# core_manual.net
KiCad netlist of a schematic drawn in EAGLE
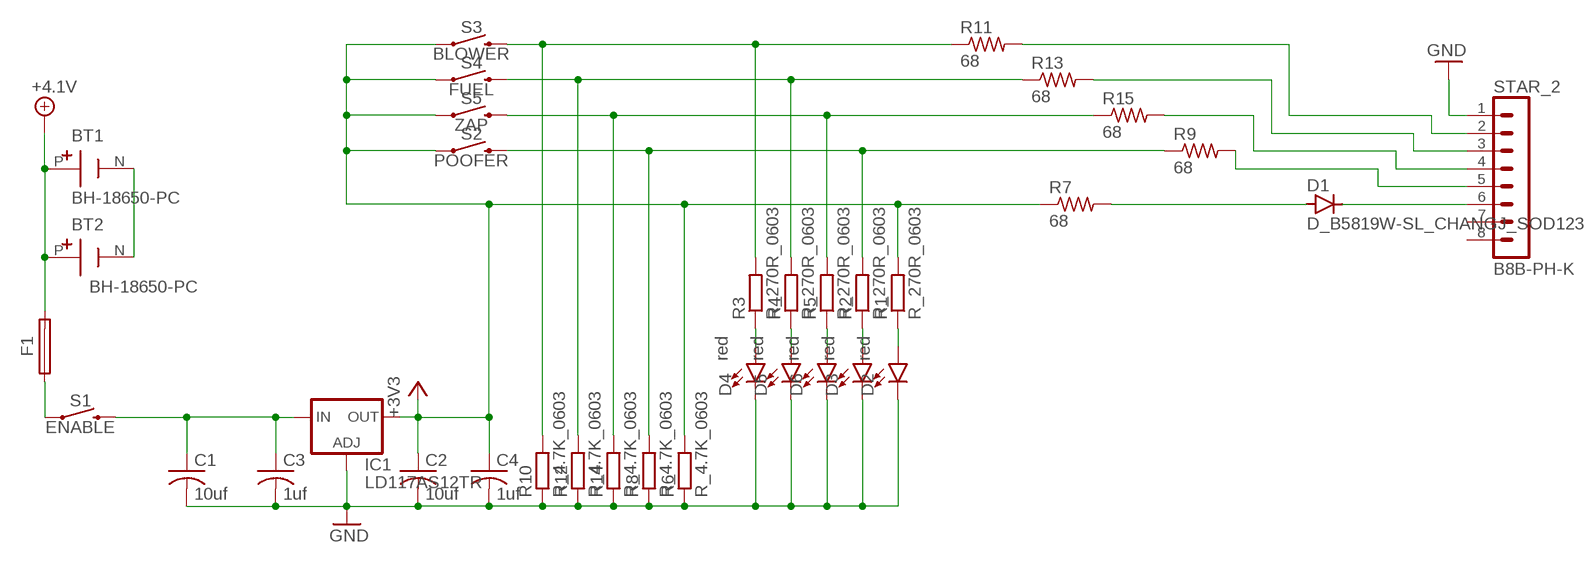
[diagram p0: schematic, sheet 1]

(export (version "E")
  (design (tool "Eeschema 10.0.6"))
  (components
    (comp (ref "BT1")
      (value "BH-18650-PC")
      (footprint "eagle-import:BAT_BH-18650-PC")
      (fields (field (name "MF") "MPD"))
      (libsource (lib "eagle-import") (part "BH-18650-PC"))
    )
    (comp (ref "BT2")
      (value "BH-18650-PC")
      (footprint "eagle-import:BAT_BH-18650-PC")
      (fields (field (name "MF") "MPD"))
      (libsource (lib "eagle-import") (part "BH-18650-PC"))
    )
    (comp (ref "C1")
      (value "10uf")
      (footprint "eagle-import:C0603")
      (fields (field (name "LCSC_PART") "C19702"))
      (libsource (lib "eagle-import") (part "C-USC0603"))
    )
    (comp (ref "C2")
      (value "10uf")
      (footprint "eagle-import:C0603")
      (fields (field (name "LCSC_PART") "C19702"))
      (libsource (lib "eagle-import") (part "C-USC0603"))
    )
    (comp (ref "C3")
      (value "1uf")
      (footprint "eagle-import:C0805")
      (fields (field (name "LCSC_PART") "C15849"))
      (libsource (lib "eagle-import") (part "C-USC0805"))
    )
    (comp (ref "C4")
      (value "1uf")
      (footprint "eagle-import:C0805")
      (fields (field (name "LCSC_PART") "C15849"))
      (libsource (lib "eagle-import") (part "C-USC0805"))
    )
    (comp (ref "D1")
      (value "D_B5819W-SL_CHANGJ_SOD123")
      (footprint "eagle-import:SOD123")
      (fields (field (name "LCSC_PART") "C8598"))
      (libsource (lib "eagle-import") (part "D__SOD123B5819W-SL_CHANGJ"))
    )
    (comp (ref "D2")
      (value "red")
      (footprint "eagle-import:LED-0603")
      (fields (field (name "LCSC_PART") "C2286"))
      (libsource (lib "eagle-import") (part "LED0603"))
    )
    (comp (ref "D3")
      (value "red")
      (footprint "eagle-import:LED-0603")
      (fields (field (name "LCSC_PART") "C2286"))
      (libsource (lib "eagle-import") (part "LED0603"))
    )
    (comp (ref "D4")
      (value "red")
      (footprint "eagle-import:LED-0603")
      (fields (field (name "LCSC_PART") "C2286"))
      (libsource (lib "eagle-import") (part "LED0603"))
    )
    (comp (ref "D5")
      (value "red")
      (footprint "eagle-import:LED-0603")
      (fields (field (name "LCSC_PART") "C2286"))
      (libsource (lib "eagle-import") (part "LED0603"))
    )
    (comp (ref "D6")
      (value "red")
      (footprint "eagle-import:LED-0603")
      (fields (field (name "LCSC_PART") "C2286"))
      (libsource (lib "eagle-import") (part "LED0603"))
    )
    (comp (ref "F1")
      (value "MF-MSMF-STYLE2_1")
      (footprint "eagle-import:FUSC4632X160")
      (fields
        (field (name "MANUFACTURER") "BOURNS")
        (field (name "MPN") "MF-MSMF")
        (field (name "LCSC_PART") "C78695")
      )
      (libsource (lib "eagle-import") (part "MF-MSMF-STYLE2_1"))
    )
    (comp (ref "IC1")
      (value "LD117AS12TR")
      (footprint "eagle-import:SOT223")
      (fields (field (name "LCSC_PART") "C347222"))
      (libsource (lib "eagle-import") (part "LD117A?S12TR"))
    )
    (comp (ref "R1")
      (value "R_270R_0603")
      (footprint "eagle-import:R0603")
      (fields (field (name "LCSC_PART") "C22966"))
      (libsource (lib "eagle-import") (part "R__0603270R"))
    )
    (comp (ref "R2")
      (value "R_270R_0603")
      (footprint "eagle-import:R0603")
      (fields (field (name "LCSC_PART") "C22966"))
      (libsource (lib "eagle-import") (part "R__0603270R"))
    )
    (comp (ref "R3")
      (value "R_270R_0603")
      (footprint "eagle-import:R0603")
      (fields (field (name "LCSC_PART") "C22966"))
      (libsource (lib "eagle-import") (part "R__0603270R"))
    )
    (comp (ref "R4")
      (value "R_270R_0603")
      (footprint "eagle-import:R0603")
      (fields (field (name "LCSC_PART") "C22966"))
      (libsource (lib "eagle-import") (part "R__0603270R"))
    )
    (comp (ref "R5")
      (value "R_270R_0603")
      (footprint "eagle-import:R0603")
      (fields (field (name "LCSC_PART") "C22966"))
      (libsource (lib "eagle-import") (part "R__0603270R"))
    )
    (comp (ref "R6")
      (value "R_4.7K_0603")
      (footprint "eagle-import:R0603")
      (fields (field (name "LCSC_PART") "C23162"))
      (libsource (lib "eagle-import") (part "R__06034.7K"))
    )
    (comp (ref "R7")
      (value "68")
      (footprint "eagle-import:R0603")
      (fields (field (name "LCSC_PART") "c27592"))
      (libsource (lib "eagle-import") (part "R-US_R0603"))
    )
    (comp (ref "R8")
      (value "R_4.7K_0603")
      (footprint "eagle-import:R0603")
      (fields (field (name "LCSC_PART") "C23162"))
      (libsource (lib "eagle-import") (part "R__06034.7K"))
    )
    (comp (ref "R9")
      (value "68")
      (footprint "eagle-import:R0603")
      (fields (field (name "LCSC_PART") "c27592"))
      (libsource (lib "eagle-import") (part "R-US_R0603"))
    )
    (comp (ref "R10")
      (value "R_4.7K_0603")
      (footprint "eagle-import:R0603")
      (fields (field (name "LCSC_PART") "C23162"))
      (libsource (lib "eagle-import") (part "R__06034.7K"))
    )
    (comp (ref "R11")
      (value "68")
      (footprint "eagle-import:R0603")
      (fields (field (name "LCSC_PART") "c27592"))
      (libsource (lib "eagle-import") (part "R-US_R0603"))
    )
    (comp (ref "R12")
      (value "R_4.7K_0603")
      (footprint "eagle-import:R0603")
      (fields (field (name "LCSC_PART") "C23162"))
      (libsource (lib "eagle-import") (part "R__06034.7K"))
    )
    (comp (ref "R13")
      (value "68")
      (footprint "eagle-import:R0603")
      (fields (field (name "LCSC_PART") "c27592"))
      (libsource (lib "eagle-import") (part "R-US_R0603"))
    )
    (comp (ref "R14")
      (value "R_4.7K_0603")
      (footprint "eagle-import:R0603")
      (fields (field (name "LCSC_PART") "C23162"))
      (libsource (lib "eagle-import") (part "R__06034.7K"))
    )
    (comp (ref "R15")
      (value "68")
      (footprint "eagle-import:R0603")
      (fields (field (name "LCSC_PART") "c27592"))
      (libsource (lib "eagle-import") (part "R-US_R0603"))
    )
    (comp (ref "S1")
      (value "ENABLE")
      (footprint "eagle-import:TACTILE_SWITCH_PTH_6.0MM")
      (libsource (lib "eagle-import") (part "MOMENTARY-SWITCH-SPST-PTH-6.0MM"))
    )
    (comp (ref "S2")
      (value "POOFER")
      (footprint "eagle-import:TACTILE_SWITCH_PTH_6.0MM")
      (libsource (lib "eagle-import") (part "MOMENTARY-SWITCH-SPST-PTH-6.0MM"))
    )
    (comp (ref "S3")
      (value "BLOWER")
      (footprint "eagle-import:TACTILE_SWITCH_PTH_6.0MM")
      (libsource (lib "eagle-import") (part "MOMENTARY-SWITCH-SPST-PTH-6.0MM"))
    )
    (comp (ref "S4")
      (value "FUEL")
      (footprint "eagle-import:TACTILE_SWITCH_PTH_6.0MM")
      (libsource (lib "eagle-import") (part "MOMENTARY-SWITCH-SPST-PTH-6.0MM"))
    )
    (comp (ref "S5")
      (value "ZAP")
      (footprint "eagle-import:TACTILE_SWITCH_PTH_6.0MM")
      (libsource (lib "eagle-import") (part "MOMENTARY-SWITCH-SPST-PTH-6.0MM"))
    )
    (comp (ref "STAR_2")
      (value "B8B-PH-K")
      (footprint "eagle-import:B8B-PH-K")
      (libsource (lib "eagle-import") (part "B8B-PH-K"))
    )
  )
  (nets
    (net (code "1") (name "+3V3") (class "Default")
      (node (ref "C2") (pin "1") (pinfunction "1_1") (pintype "passive"))
      (node (ref "C4") (pin "1") (pinfunction "1_1") (pintype "passive"))
      (node (ref "IC1") (pin "4") (pinfunction "OUT_4") (pintype "passive"))
      (node (ref "R1") (pin "2") (pinfunction "2_2") (pintype "passive"))
      (node (ref "R6") (pin "2") (pinfunction "2_2") (pintype "passive"))
      (node (ref "R7") (pin "1") (pinfunction "1_1") (pintype "passive"))
      (node (ref "S2") (pin "1") (pinfunction "1_1") (pintype "passive"))
      (node (ref "S3") (pin "1") (pinfunction "1_1") (pintype "passive"))
      (node (ref "S4") (pin "1") (pinfunction "1_1") (pintype "passive"))
      (node (ref "S5") (pin "1") (pinfunction "1_1") (pintype "passive"))
    )
    (net (code "2") (name "+4.1V") (class "Default")
      (node (ref "BT1") (pin "P") (pinfunction "+_P") (pintype "passive"))
      (node (ref "BT2") (pin "P") (pinfunction "+_P") (pintype "passive"))
      (node (ref "F1") (pin "2") (pinfunction "2_2") (pintype "passive"))
    )
    (net (code "3") (name "GND") (class "Default")
      (node (ref "C1") (pin "2") (pinfunction "2_2") (pintype "passive"))
      (node (ref "C2") (pin "2") (pinfunction "2_2") (pintype "passive"))
      (node (ref "C3") (pin "2") (pinfunction "2_2") (pintype "passive"))
      (node (ref "C4") (pin "2") (pinfunction "2_2") (pintype "passive"))
      (node (ref "D2") (pin "C") (pinfunction "C_C") (pintype "passive"))
      (node (ref "D3") (pin "C") (pinfunction "C_C") (pintype "passive"))
      (node (ref "D4") (pin "C") (pinfunction "C_C") (pintype "passive"))
      (node (ref "D5") (pin "C") (pinfunction "C_C") (pintype "passive"))
      (node (ref "D6") (pin "C") (pinfunction "C_C") (pintype "passive"))
      (node (ref "IC1") (pin "1") (pinfunction "ADJ_1") (pintype "input"))
      (node (ref "R10") (pin "1") (pinfunction "1_1") (pintype "passive"))
      (node (ref "R12") (pin "1") (pinfunction "1_1") (pintype "passive"))
      (node (ref "R14") (pin "1") (pinfunction "1_1") (pintype "passive"))
      (node (ref "R6") (pin "1") (pinfunction "1_1") (pintype "passive"))
      (node (ref "R8") (pin "1") (pinfunction "1_1") (pintype "passive"))
      (node (ref "STAR_2") (pin "1") (pinfunction "1_1") (pintype "passive"))
    )
    (net (code "4") (name "Net-(BT1--)") (class "Default")
      (node (ref "BT1") (pin "N") (pinfunction "-_N") (pintype "passive"))
      (node (ref "BT2") (pin "N") (pinfunction "-_N") (pintype "passive"))
    )
    (net (code "5") (name "Net-(D1-PadA)") (class "Default")
      (node (ref "D1") (pin "A") (pinfunction "A_A") (pintype "passive"))
      (node (ref "R7") (pin "2") (pinfunction "2_2") (pintype "passive"))
    )
    (net (code "6") (name "Net-(D1-PadC)") (class "Default")
      (node (ref "D1") (pin "C") (pinfunction "C_C") (pintype "passive"))
      (node (ref "STAR_2") (pin "6") (pinfunction "6_6") (pintype "passive"))
    )
    (net (code "7") (name "Net-(D2-PadA)") (class "Default")
      (node (ref "D2") (pin "A") (pinfunction "A_A") (pintype "passive"))
      (node (ref "R1") (pin "1") (pinfunction "1_1") (pintype "passive"))
    )
    (net (code "8") (name "Net-(D3-PadA)") (class "Default")
      (node (ref "D3") (pin "A") (pinfunction "A_A") (pintype "passive"))
      (node (ref "R2") (pin "1") (pinfunction "1_1") (pintype "passive"))
    )
    (net (code "9") (name "Net-(D4-PadA)") (class "Default")
      (node (ref "D4") (pin "A") (pinfunction "A_A") (pintype "passive"))
      (node (ref "R3") (pin "1") (pinfunction "1_1") (pintype "passive"))
    )
    (net (code "10") (name "Net-(D5-PadA)") (class "Default")
      (node (ref "D5") (pin "A") (pinfunction "A_A") (pintype "passive"))
      (node (ref "R4") (pin "1") (pinfunction "1_1") (pintype "passive"))
    )
    (net (code "11") (name "Net-(D6-PadA)") (class "Default")
      (node (ref "D6") (pin "A") (pinfunction "A_A") (pintype "passive"))
      (node (ref "R5") (pin "1") (pinfunction "1_1") (pintype "passive"))
    )
    (net (code "12") (name "Net-(F1-Pad1)") (class "Default")
      (node (ref "F1") (pin "1") (pinfunction "1_1") (pintype "passive"))
      (node (ref "S1") (pin "1") (pinfunction "1_1") (pintype "passive"))
    )
    (net (code "13") (name "Net-(IC1-IN)") (class "Default")
      (node (ref "C1") (pin "1") (pinfunction "1_1") (pintype "passive"))
      (node (ref "C3") (pin "1") (pinfunction "1_1") (pintype "passive"))
      (node (ref "IC1") (pin "3") (pinfunction "IN_3") (pintype "input"))
      (node (ref "S1") (pin "3") (pinfunction "2_3") (pintype "passive"))
    )
    (net (code "14") (name "Net-(R9-Pad2)") (class "Default")
      (node (ref "R9") (pin "2") (pinfunction "2_2") (pintype "passive"))
      (node (ref "STAR_2") (pin "5") (pinfunction "5_5") (pintype "passive"))
    )
    (net (code "15") (name "Net-(R11-Pad2)") (class "Default")
      (node (ref "R11") (pin "2") (pinfunction "2_2") (pintype "passive"))
      (node (ref "STAR_2") (pin "2") (pinfunction "2_2") (pintype "passive"))
    )
    (net (code "16") (name "Net-(R13-Pad2)") (class "Default")
      (node (ref "R13") (pin "2") (pinfunction "2_2") (pintype "passive"))
      (node (ref "STAR_2") (pin "3") (pinfunction "3_3") (pintype "passive"))
    )
    (net (code "17") (name "Net-(R15-Pad2)") (class "Default")
      (node (ref "R15") (pin "2") (pinfunction "2_2") (pintype "passive"))
      (node (ref "STAR_2") (pin "4") (pinfunction "4_4") (pintype "passive"))
    )
    (net (code "18") (name "Net-(S2-2)") (class "Default")
      (node (ref "R2") (pin "2") (pinfunction "2_2") (pintype "passive"))
      (node (ref "R8") (pin "2") (pinfunction "2_2") (pintype "passive"))
      (node (ref "R9") (pin "1") (pinfunction "1_1") (pintype "passive"))
      (node (ref "S2") (pin "3") (pinfunction "2_3") (pintype "passive"))
    )
    (net (code "19") (name "Net-(S3-2)") (class "Default")
      (node (ref "R10") (pin "2") (pinfunction "2_2") (pintype "passive"))
      (node (ref "R11") (pin "1") (pinfunction "1_1") (pintype "passive"))
      (node (ref "R3") (pin "2") (pinfunction "2_2") (pintype "passive"))
      (node (ref "S3") (pin "3") (pinfunction "2_3") (pintype "passive"))
    )
    (net (code "20") (name "Net-(S4-2)") (class "Default")
      (node (ref "R12") (pin "2") (pinfunction "2_2") (pintype "passive"))
      (node (ref "R13") (pin "1") (pinfunction "1_1") (pintype "passive"))
      (node (ref "R4") (pin "2") (pinfunction "2_2") (pintype "passive"))
      (node (ref "S4") (pin "3") (pinfunction "2_3") (pintype "passive"))
    )
    (net (code "21") (name "Net-(S5-2)") (class "Default")
      (node (ref "R14") (pin "2") (pinfunction "2_2") (pintype "passive"))
      (node (ref "R15") (pin "1") (pinfunction "1_1") (pintype "passive"))
      (node (ref "R5") (pin "2") (pinfunction "2_2") (pintype "passive"))
      (node (ref "S5") (pin "3") (pinfunction "2_3") (pintype "passive"))
    )
    (net (code "22") (name "unconnected-(STAR_2-Pad7)") (class "Default")
      (node (ref "STAR_2") (pin "7") (pinfunction "7_7") (pintype "passive"))
    )
    (net (code "23") (name "unconnected-(STAR_2-Pad8)") (class "Default")
      (node (ref "STAR_2") (pin "8") (pinfunction "8_8") (pintype "passive"))
    )
  )
)
